# slider.net
KiCad netlist of a schematic drawn in EAGLE
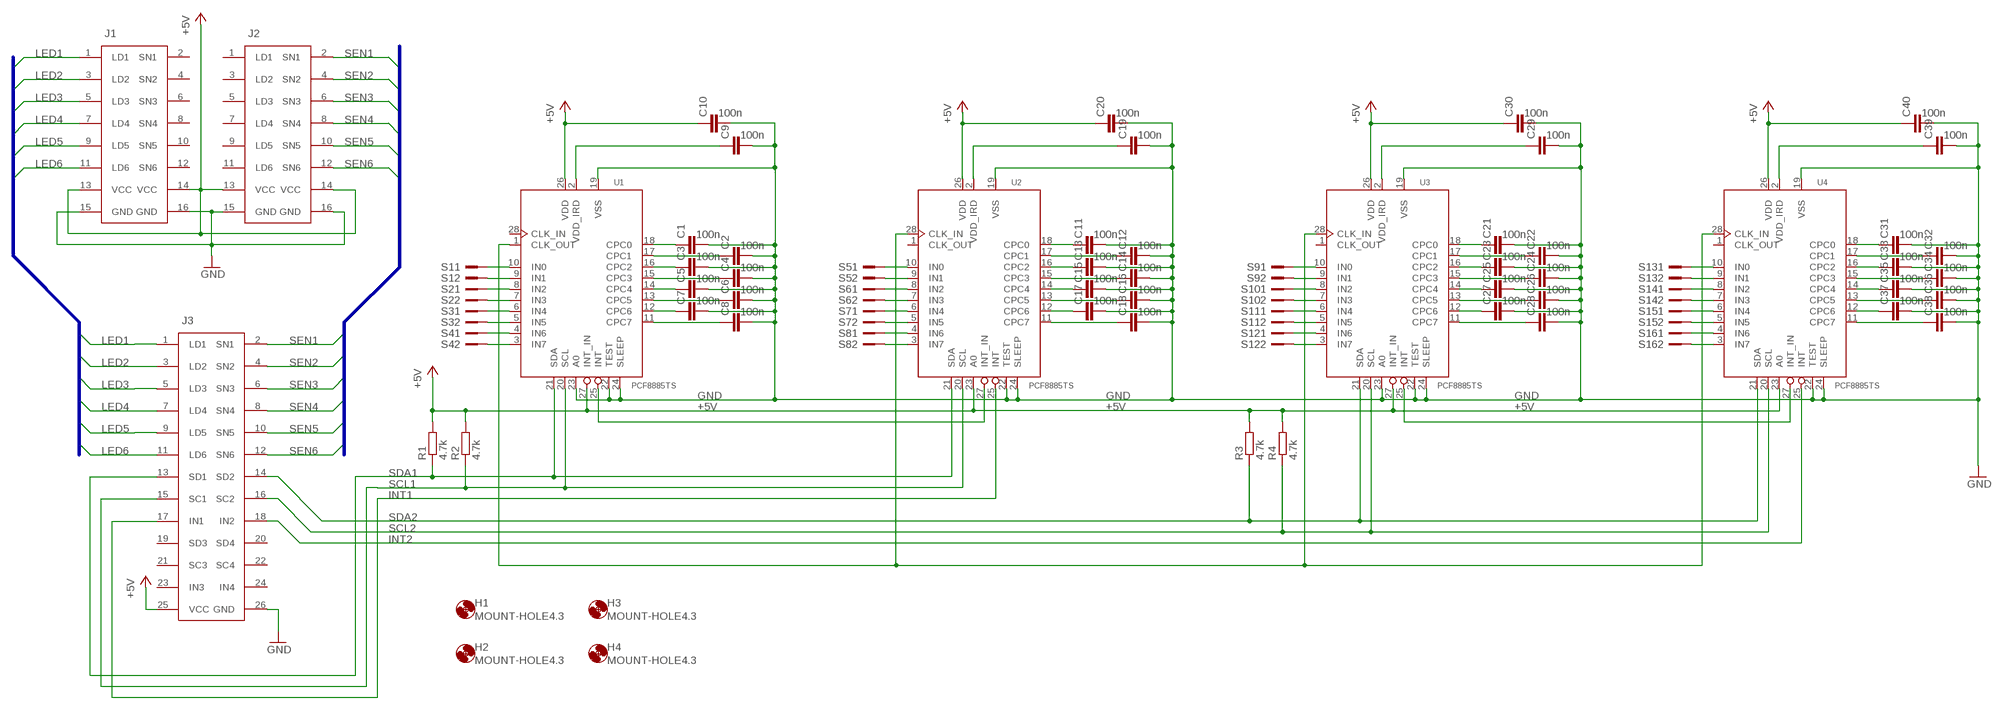
[diagram p0: schematic, sheet 1]

(export (version "E")
  (design (tool "Eeschema 10.0.6"))
  (components
    (comp (ref "C1")
      (value "100n")
      (footprint "eagle-import:C0603K")
      (libsource (lib "eagle-import") (part "C-EUC0603K"))
    )
    (comp (ref "C2")
      (value "100n")
      (footprint "eagle-import:C0603K")
      (libsource (lib "eagle-import") (part "C-EUC0603K"))
    )
    (comp (ref "C3")
      (value "100n")
      (footprint "eagle-import:C0603K")
      (libsource (lib "eagle-import") (part "C-EUC0603K"))
    )
    (comp (ref "C4")
      (value "100n")
      (footprint "eagle-import:C0603K")
      (libsource (lib "eagle-import") (part "C-EUC0603K"))
    )
    (comp (ref "C5")
      (value "100n")
      (footprint "eagle-import:C0603K")
      (libsource (lib "eagle-import") (part "C-EUC0603K"))
    )
    (comp (ref "C6")
      (value "100n")
      (footprint "eagle-import:C0603K")
      (libsource (lib "eagle-import") (part "C-EUC0603K"))
    )
    (comp (ref "C7")
      (value "100n")
      (footprint "eagle-import:C0603K")
      (libsource (lib "eagle-import") (part "C-EUC0603K"))
    )
    (comp (ref "C8")
      (value "100n")
      (footprint "eagle-import:C0603K")
      (libsource (lib "eagle-import") (part "C-EUC0603K"))
    )
    (comp (ref "C9")
      (value "100n")
      (footprint "eagle-import:C0603K")
      (libsource (lib "eagle-import") (part "C-EUC0603K"))
    )
    (comp (ref "C10")
      (value "100n")
      (footprint "eagle-import:C0603K")
      (libsource (lib "eagle-import") (part "C-EUC0603K"))
    )
    (comp (ref "C11")
      (value "100n")
      (footprint "eagle-import:C0603K")
      (libsource (lib "eagle-import") (part "C-EUC0603K"))
    )
    (comp (ref "C12")
      (value "100n")
      (footprint "eagle-import:C0603K")
      (libsource (lib "eagle-import") (part "C-EUC0603K"))
    )
    (comp (ref "C13")
      (value "100n")
      (footprint "eagle-import:C0603K")
      (libsource (lib "eagle-import") (part "C-EUC0603K"))
    )
    (comp (ref "C14")
      (value "100n")
      (footprint "eagle-import:C0603K")
      (libsource (lib "eagle-import") (part "C-EUC0603K"))
    )
    (comp (ref "C15")
      (value "100n")
      (footprint "eagle-import:C0603K")
      (libsource (lib "eagle-import") (part "C-EUC0603K"))
    )
    (comp (ref "C16")
      (value "100n")
      (footprint "eagle-import:C0603K")
      (libsource (lib "eagle-import") (part "C-EUC0603K"))
    )
    (comp (ref "C17")
      (value "100n")
      (footprint "eagle-import:C0603K")
      (libsource (lib "eagle-import") (part "C-EUC0603K"))
    )
    (comp (ref "C18")
      (value "100n")
      (footprint "eagle-import:C0603K")
      (libsource (lib "eagle-import") (part "C-EUC0603K"))
    )
    (comp (ref "C19")
      (value "100n")
      (footprint "eagle-import:C0603K")
      (libsource (lib "eagle-import") (part "C-EUC0603K"))
    )
    (comp (ref "C20")
      (value "100n")
      (footprint "eagle-import:C0603K")
      (libsource (lib "eagle-import") (part "C-EUC0603K"))
    )
    (comp (ref "C21")
      (value "100n")
      (footprint "eagle-import:C0603K")
      (libsource (lib "eagle-import") (part "C-EUC0603K"))
    )
    (comp (ref "C22")
      (value "100n")
      (footprint "eagle-import:C0603K")
      (libsource (lib "eagle-import") (part "C-EUC0603K"))
    )
    (comp (ref "C23")
      (value "100n")
      (footprint "eagle-import:C0603K")
      (libsource (lib "eagle-import") (part "C-EUC0603K"))
    )
    (comp (ref "C24")
      (value "100n")
      (footprint "eagle-import:C0603K")
      (libsource (lib "eagle-import") (part "C-EUC0603K"))
    )
    (comp (ref "C25")
      (value "100n")
      (footprint "eagle-import:C0603K")
      (libsource (lib "eagle-import") (part "C-EUC0603K"))
    )
    (comp (ref "C26")
      (value "100n")
      (footprint "eagle-import:C0603K")
      (libsource (lib "eagle-import") (part "C-EUC0603K"))
    )
    (comp (ref "C27")
      (value "100n")
      (footprint "eagle-import:C0603K")
      (libsource (lib "eagle-import") (part "C-EUC0603K"))
    )
    (comp (ref "C28")
      (value "100n")
      (footprint "eagle-import:C0603K")
      (libsource (lib "eagle-import") (part "C-EUC0603K"))
    )
    (comp (ref "C29")
      (value "100n")
      (footprint "eagle-import:C0603K")
      (libsource (lib "eagle-import") (part "C-EUC0603K"))
    )
    (comp (ref "C30")
      (value "100n")
      (footprint "eagle-import:C0603K")
      (libsource (lib "eagle-import") (part "C-EUC0603K"))
    )
    (comp (ref "C31")
      (value "100n")
      (footprint "eagle-import:C0603K")
      (libsource (lib "eagle-import") (part "C-EUC0603K"))
    )
    (comp (ref "C32")
      (value "100n")
      (footprint "eagle-import:C0603K")
      (libsource (lib "eagle-import") (part "C-EUC0603K"))
    )
    (comp (ref "C33")
      (value "100n")
      (footprint "eagle-import:C0603K")
      (libsource (lib "eagle-import") (part "C-EUC0603K"))
    )
    (comp (ref "C34")
      (value "100n")
      (footprint "eagle-import:C0603K")
      (libsource (lib "eagle-import") (part "C-EUC0603K"))
    )
    (comp (ref "C35")
      (value "100n")
      (footprint "eagle-import:C0603K")
      (libsource (lib "eagle-import") (part "C-EUC0603K"))
    )
    (comp (ref "C36")
      (value "100n")
      (footprint "eagle-import:C0603K")
      (libsource (lib "eagle-import") (part "C-EUC0603K"))
    )
    (comp (ref "C37")
      (value "100n")
      (footprint "eagle-import:C0603K")
      (libsource (lib "eagle-import") (part "C-EUC0603K"))
    )
    (comp (ref "C38")
      (value "100n")
      (footprint "eagle-import:C0603K")
      (libsource (lib "eagle-import") (part "C-EUC0603K"))
    )
    (comp (ref "C39")
      (value "100n")
      (footprint "eagle-import:C0603K")
      (libsource (lib "eagle-import") (part "C-EUC0603K"))
    )
    (comp (ref "C40")
      (value "100n")
      (footprint "eagle-import:C0603K")
      (libsource (lib "eagle-import") (part "C-EUC0603K"))
    )
    (comp (ref "H1")
      (value "MOUNT-HOLE4.3")
      (footprint "eagle-import:4,3")
      (libsource (lib "eagle-import") (part "MOUNT-HOLE4.3"))
    )
    (comp (ref "H2")
      (value "MOUNT-HOLE4.3")
      (footprint "eagle-import:4,3")
      (libsource (lib "eagle-import") (part "MOUNT-HOLE4.3"))
    )
    (comp (ref "H3")
      (value "MOUNT-HOLE4.3")
      (footprint "eagle-import:4,3")
      (libsource (lib "eagle-import") (part "MOUNT-HOLE4.3"))
    )
    (comp (ref "H4")
      (value "MOUNT-HOLE4.3")
      (footprint "eagle-import:4,3")
      (libsource (lib "eagle-import") (part "MOUNT-HOLE4.3"))
    )
    (comp (ref "J1")
      (value "2516-SMD-AIR")
      (footprint "eagle-import:612X1620621")
      (libsource (lib "eagle-import") (part "2516-SMD-AIR"))
    )
    (comp (ref "J2")
      (value "2516-SMD-AIR")
      (footprint "eagle-import:612X1620621")
      (libsource (lib "eagle-import") (part "2516-SMD-AIR"))
    )
    (comp (ref "J3")
      (value "2526-SMD-MCU")
      (footprint "eagle-import:612X2620621")
      (libsource (lib "eagle-import") (part "2526-SMD-MCU"))
    )
    (comp (ref "R1")
      (value "4.7k")
      (footprint "eagle-import:R0805")
      (libsource (lib "eagle-import") (part "R-EU_R0805"))
    )
    (comp (ref "R2")
      (value "4.7k")
      (footprint "eagle-import:R0805")
      (libsource (lib "eagle-import") (part "R-EU_R0805"))
    )
    (comp (ref "R3")
      (value "4.7k")
      (footprint "eagle-import:R0805")
      (libsource (lib "eagle-import") (part "R-EU_R0805"))
    )
    (comp (ref "R4")
      (value "4.7k")
      (footprint "eagle-import:R0805")
      (libsource (lib "eagle-import") (part "R-EU_R0805"))
    )
    (comp (ref "S1")
      (value "SENSPAD")
      (footprint "eagle-import:SENSPAD")
      (libsource (lib "eagle-import") (part "SENSPAD"))
    )
    (comp (ref "S2")
      (value "SENSPAD")
      (footprint "eagle-import:SENSPAD")
      (libsource (lib "eagle-import") (part "SENSPAD"))
    )
    (comp (ref "S3")
      (value "SENSPAD")
      (footprint "eagle-import:SENSPAD")
      (libsource (lib "eagle-import") (part "SENSPAD"))
    )
    (comp (ref "S4")
      (value "SENSPAD")
      (footprint "eagle-import:SENSPAD")
      (libsource (lib "eagle-import") (part "SENSPAD"))
    )
    (comp (ref "S5")
      (value "SENSPAD")
      (footprint "eagle-import:SENSPAD")
      (libsource (lib "eagle-import") (part "SENSPAD"))
    )
    (comp (ref "S6")
      (value "SENSPAD")
      (footprint "eagle-import:SENSPAD")
      (libsource (lib "eagle-import") (part "SENSPAD"))
    )
    (comp (ref "S7")
      (value "SENSPAD")
      (footprint "eagle-import:SENSPAD")
      (libsource (lib "eagle-import") (part "SENSPAD"))
    )
    (comp (ref "S8")
      (value "SENSPAD")
      (footprint "eagle-import:SENSPAD")
      (libsource (lib "eagle-import") (part "SENSPAD"))
    )
    (comp (ref "S9")
      (value "SENSPAD")
      (footprint "eagle-import:SENSPAD")
      (libsource (lib "eagle-import") (part "SENSPAD"))
    )
    (comp (ref "S10")
      (value "SENSPAD")
      (footprint "eagle-import:SENSPAD")
      (libsource (lib "eagle-import") (part "SENSPAD"))
    )
    (comp (ref "S11")
      (value "SENSPAD")
      (footprint "eagle-import:SENSPAD")
      (libsource (lib "eagle-import") (part "SENSPAD"))
    )
    (comp (ref "S12")
      (value "SENSPAD")
      (footprint "eagle-import:SENSPAD")
      (libsource (lib "eagle-import") (part "SENSPAD"))
    )
    (comp (ref "S13")
      (value "SENSPAD")
      (footprint "eagle-import:SENSPAD")
      (libsource (lib "eagle-import") (part "SENSPAD"))
    )
    (comp (ref "S14")
      (value "SENSPAD")
      (footprint "eagle-import:SENSPAD")
      (libsource (lib "eagle-import") (part "SENSPAD"))
    )
    (comp (ref "S15")
      (value "SENSPAD")
      (footprint "eagle-import:SENSPAD")
      (libsource (lib "eagle-import") (part "SENSPAD"))
    )
    (comp (ref "S16")
      (value "SENSPAD")
      (footprint "eagle-import:SENSPAD")
      (libsource (lib "eagle-import") (part "SENSPAD"))
    )
    (comp (ref "U1")
      (value "PCF8885TS")
      (footprint "eagle-import:SOT361-1")
      (libsource (lib "eagle-import") (part "PCF8885TS"))
    )
    (comp (ref "U2")
      (value "PCF8885TS")
      (footprint "eagle-import:SOT361-1")
      (libsource (lib "eagle-import") (part "PCF8885TS"))
    )
    (comp (ref "U3")
      (value "PCF8885TS")
      (footprint "eagle-import:SOT361-1")
      (libsource (lib "eagle-import") (part "PCF8885TS"))
    )
    (comp (ref "U4")
      (value "PCF8885TS")
      (footprint "eagle-import:SOT361-1")
      (libsource (lib "eagle-import") (part "PCF8885TS"))
    )
  )
  (nets
    (net (code "1") (name "+5V") (class "Default")
      (node (ref "C10") (pin "1") (pinfunction "1_1") (pintype "passive"))
      (node (ref "C20") (pin "1") (pinfunction "1_1") (pintype "passive"))
      (node (ref "C30") (pin "1") (pinfunction "1_1") (pintype "passive"))
      (node (ref "C40") (pin "1") (pinfunction "1_1") (pintype "passive"))
      (node (ref "J1") (pin "13") (pinfunction "VCC_13") (pintype "passive"))
      (node (ref "J1") (pin "14") (pinfunction "VCC_14") (pintype "passive"))
      (node (ref "J2") (pin "13") (pinfunction "VCC_13") (pintype "passive"))
      (node (ref "J2") (pin "14") (pinfunction "VCC_14") (pintype "passive"))
      (node (ref "J3") (pin "25") (pinfunction "VCC_25") (pintype "passive"))
      (node (ref "R1") (pin "2") (pinfunction "2_2") (pintype "passive"))
      (node (ref "R2") (pin "2") (pinfunction "2_2") (pintype "passive"))
      (node (ref "R3") (pin "2") (pinfunction "2_2") (pintype "passive"))
      (node (ref "R4") (pin "2") (pinfunction "2_2") (pintype "passive"))
      (node (ref "U1") (pin "26") (pinfunction "VDD_26") (pintype "power_in"))
      (node (ref "U1") (pin "27") (pinfunction "INT_IN_27") (pintype "input"))
      (node (ref "U2") (pin "23") (pinfunction "A0_23") (pintype "input"))
      (node (ref "U2") (pin "26") (pinfunction "VDD_26") (pintype "power_in"))
      (node (ref "U3") (pin "26") (pinfunction "VDD_26") (pintype "power_in"))
      (node (ref "U3") (pin "27") (pinfunction "INT_IN_27") (pintype "input"))
      (node (ref "U4") (pin "23") (pinfunction "A0_23") (pintype "input"))
      (node (ref "U4") (pin "26") (pinfunction "VDD_26") (pintype "power_in"))
    )
    (net (code "2") (name "/INT1") (class "Default")
      (node (ref "J3") (pin "17") (pinfunction "IN1_17") (pintype "passive"))
      (node (ref "U2") (pin "25") (pinfunction "INT_25") (pintype "output"))
    )
    (net (code "3") (name "/INT2") (class "Default")
      (node (ref "J3") (pin "18") (pinfunction "IN2_18") (pintype "passive"))
      (node (ref "U4") (pin "25") (pinfunction "INT_25") (pintype "output"))
    )
    (net (code "4") (name "/LED1") (class "Default")
      (node (ref "J1") (pin "1") (pinfunction "LD1_1") (pintype "passive"))
      (node (ref "J3") (pin "1") (pinfunction "LD1_1") (pintype "passive"))
    )
    (net (code "5") (name "/LED2") (class "Default")
      (node (ref "J1") (pin "3") (pinfunction "LD2_3") (pintype "passive"))
      (node (ref "J3") (pin "3") (pinfunction "LD2_3") (pintype "passive"))
    )
    (net (code "6") (name "/LED3") (class "Default")
      (node (ref "J1") (pin "5") (pinfunction "LD3_5") (pintype "passive"))
      (node (ref "J3") (pin "5") (pinfunction "LD3_5") (pintype "passive"))
    )
    (net (code "7") (name "/LED4") (class "Default")
      (node (ref "J1") (pin "7") (pinfunction "LD4_7") (pintype "passive"))
      (node (ref "J3") (pin "7") (pinfunction "LD4_7") (pintype "passive"))
    )
    (net (code "8") (name "/LED5") (class "Default")
      (node (ref "J1") (pin "9") (pinfunction "LD5_9") (pintype "passive"))
      (node (ref "J3") (pin "9") (pinfunction "LD5_9") (pintype "passive"))
    )
    (net (code "9") (name "/LED6") (class "Default")
      (node (ref "J1") (pin "11") (pinfunction "LD6_11") (pintype "passive"))
      (node (ref "J3") (pin "11") (pinfunction "LD6_11") (pintype "passive"))
    )
    (net (code "10") (name "/SCL1") (class "Default")
      (node (ref "J3") (pin "15") (pinfunction "SC1_15") (pintype "passive"))
      (node (ref "R2") (pin "1") (pinfunction "1_1") (pintype "passive"))
      (node (ref "U1") (pin "20") (pinfunction "SCL_20") (pintype "input"))
      (node (ref "U2") (pin "20") (pinfunction "SCL_20") (pintype "input"))
    )
    (net (code "11") (name "/SCL2") (class "Default")
      (node (ref "J3") (pin "16") (pinfunction "SC2_16") (pintype "passive"))
      (node (ref "R4") (pin "1") (pinfunction "1_1") (pintype "passive"))
      (node (ref "U3") (pin "20") (pinfunction "SCL_20") (pintype "input"))
      (node (ref "U4") (pin "20") (pinfunction "SCL_20") (pintype "input"))
    )
    (net (code "12") (name "/SDA1") (class "Default")
      (node (ref "J3") (pin "13") (pinfunction "SD1_13") (pintype "passive"))
      (node (ref "R1") (pin "1") (pinfunction "1_1") (pintype "passive"))
      (node (ref "U1") (pin "21") (pinfunction "SDA_21") (pintype "bidirectional"))
      (node (ref "U2") (pin "21") (pinfunction "SDA_21") (pintype "bidirectional"))
    )
    (net (code "13") (name "/SDA2") (class "Default")
      (node (ref "J3") (pin "14") (pinfunction "SD2_14") (pintype "passive"))
      (node (ref "R3") (pin "1") (pinfunction "1_1") (pintype "passive"))
      (node (ref "U3") (pin "21") (pinfunction "SDA_21") (pintype "bidirectional"))
      (node (ref "U4") (pin "21") (pinfunction "SDA_21") (pintype "bidirectional"))
    )
    (net (code "14") (name "/SEN1") (class "Default")
      (node (ref "J2") (pin "2") (pinfunction "SN1_2") (pintype "passive"))
      (node (ref "J3") (pin "2") (pinfunction "SN1_2") (pintype "passive"))
    )
    (net (code "15") (name "/SEN2") (class "Default")
      (node (ref "J2") (pin "4") (pinfunction "SN2_4") (pintype "passive"))
      (node (ref "J3") (pin "4") (pinfunction "SN2_4") (pintype "passive"))
    )
    (net (code "16") (name "/SEN3") (class "Default")
      (node (ref "J2") (pin "6") (pinfunction "SN3_6") (pintype "passive"))
      (node (ref "J3") (pin "6") (pinfunction "SN3_6") (pintype "passive"))
    )
    (net (code "17") (name "/SEN4") (class "Default")
      (node (ref "J2") (pin "8") (pinfunction "SN4_8") (pintype "passive"))
      (node (ref "J3") (pin "8") (pinfunction "SN4_8") (pintype "passive"))
    )
    (net (code "18") (name "/SEN5") (class "Default")
      (node (ref "J2") (pin "10") (pinfunction "SN5_10") (pintype "passive"))
      (node (ref "J3") (pin "10") (pinfunction "SN5_10") (pintype "passive"))
    )
    (net (code "19") (name "/SEN6") (class "Default")
      (node (ref "J2") (pin "12") (pinfunction "SN6_12") (pintype "passive"))
      (node (ref "J3") (pin "12") (pinfunction "SN6_12") (pintype "passive"))
    )
    (net (code "20") (name "GND") (class "Default")
      (node (ref "C1") (pin "2") (pinfunction "2_2") (pintype "passive"))
      (node (ref "C10") (pin "2") (pinfunction "2_2") (pintype "passive"))
      (node (ref "C11") (pin "2") (pinfunction "2_2") (pintype "passive"))
      (node (ref "C12") (pin "2") (pinfunction "2_2") (pintype "passive"))
      (node (ref "C13") (pin "2") (pinfunction "2_2") (pintype "passive"))
      (node (ref "C14") (pin "2") (pinfunction "2_2") (pintype "passive"))
      (node (ref "C15") (pin "2") (pinfunction "2_2") (pintype "passive"))
      (node (ref "C16") (pin "2") (pinfunction "2_2") (pintype "passive"))
      (node (ref "C17") (pin "2") (pinfunction "2_2") (pintype "passive"))
      (node (ref "C18") (pin "2") (pinfunction "2_2") (pintype "passive"))
      (node (ref "C19") (pin "2") (pinfunction "2_2") (pintype "passive"))
      (node (ref "C2") (pin "2") (pinfunction "2_2") (pintype "passive"))
      (node (ref "C20") (pin "2") (pinfunction "2_2") (pintype "passive"))
      (node (ref "C21") (pin "2") (pinfunction "2_2") (pintype "passive"))
      (node (ref "C22") (pin "2") (pinfunction "2_2") (pintype "passive"))
      (node (ref "C23") (pin "2") (pinfunction "2_2") (pintype "passive"))
      (node (ref "C24") (pin "2") (pinfunction "2_2") (pintype "passive"))
      (node (ref "C25") (pin "2") (pinfunction "2_2") (pintype "passive"))
      (node (ref "C26") (pin "2") (pinfunction "2_2") (pintype "passive"))
      (node (ref "C27") (pin "2") (pinfunction "2_2") (pintype "passive"))
      (node (ref "C28") (pin "2") (pinfunction "2_2") (pintype "passive"))
      (node (ref "C29") (pin "2") (pinfunction "2_2") (pintype "passive"))
      (node (ref "C3") (pin "2") (pinfunction "2_2") (pintype "passive"))
      (node (ref "C30") (pin "2") (pinfunction "2_2") (pintype "passive"))
      (node (ref "C31") (pin "2") (pinfunction "2_2") (pintype "passive"))
      (node (ref "C32") (pin "2") (pinfunction "2_2") (pintype "passive"))
      (node (ref "C33") (pin "2") (pinfunction "2_2") (pintype "passive"))
      (node (ref "C34") (pin "2") (pinfunction "2_2") (pintype "passive"))
      (node (ref "C35") (pin "2") (pinfunction "2_2") (pintype "passive"))
      (node (ref "C36") (pin "2") (pinfunction "2_2") (pintype "passive"))
      (node (ref "C37") (pin "2") (pinfunction "2_2") (pintype "passive"))
      (node (ref "C38") (pin "2") (pinfunction "2_2") (pintype "passive"))
      (node (ref "C39") (pin "2") (pinfunction "2_2") (pintype "passive"))
      (node (ref "C4") (pin "2") (pinfunction "2_2") (pintype "passive"))
      (node (ref "C40") (pin "2") (pinfunction "2_2") (pintype "passive"))
      (node (ref "C5") (pin "2") (pinfunction "2_2") (pintype "passive"))
      (node (ref "C6") (pin "2") (pinfunction "2_2") (pintype "passive"))
      (node (ref "C7") (pin "2") (pinfunction "2_2") (pintype "passive"))
      (node (ref "C8") (pin "2") (pinfunction "2_2") (pintype "passive"))
      (node (ref "C9") (pin "2") (pinfunction "2_2") (pintype "passive"))
      (node (ref "J1") (pin "15") (pinfunction "GND_15") (pintype "passive"))
      (node (ref "J1") (pin "16") (pinfunction "GND_16") (pintype "passive"))
      (node (ref "J2") (pin "15") (pinfunction "GND_15") (pintype "passive"))
      (node (ref "J2") (pin "16") (pinfunction "GND_16") (pintype "passive"))
      (node (ref "J3") (pin "26") (pinfunction "GND_26") (pintype "passive"))
      (node (ref "U1") (pin "19") (pinfunction "VSS_19") (pintype "power_in"))
      (node (ref "U1") (pin "22") (pinfunction "TEST_22") (pintype "input"))
      (node (ref "U1") (pin "23") (pinfunction "A0_23") (pintype "input"))
      (node (ref "U1") (pin "24") (pinfunction "SLEEP_24") (pintype "input"))
      (node (ref "U2") (pin "19") (pinfunction "VSS_19") (pintype "power_in"))
      (node (ref "U2") (pin "22") (pinfunction "TEST_22") (pintype "input"))
      (node (ref "U2") (pin "24") (pinfunction "SLEEP_24") (pintype "input"))
      (node (ref "U3") (pin "19") (pinfunction "VSS_19") (pintype "power_in"))
      (node (ref "U3") (pin "22") (pinfunction "TEST_22") (pintype "input"))
      (node (ref "U3") (pin "23") (pinfunction "A0_23") (pintype "input"))
      (node (ref "U3") (pin "24") (pinfunction "SLEEP_24") (pintype "input"))
      (node (ref "U4") (pin "19") (pinfunction "VSS_19") (pintype "power_in"))
      (node (ref "U4") (pin "22") (pinfunction "TEST_22") (pintype "input"))
      (node (ref "U4") (pin "24") (pinfunction "SLEEP_24") (pintype "input"))
    )
    (net (code "21") (name "Net-(S1A-KL)") (class "Default")
      (node (ref "S1") (pin "1") (pinfunction "KL_1") (pintype "passive"))
      (node (ref "U1") (pin "10") (pinfunction "IN0_10") (pintype "input"))
    )
    (net (code "22") (name "Net-(S1B-KL)") (class "Default")
      (node (ref "S1") (pin "2") (pinfunction "KL_2") (pintype "passive"))
      (node (ref "U1") (pin "9") (pinfunction "IN1_9") (pintype "input"))
    )
    (net (code "23") (name "Net-(S2A-KL)") (class "Default")
      (node (ref "S2") (pin "1") (pinfunction "KL_1") (pintype "passive"))
      (node (ref "U1") (pin "8") (pinfunction "IN2_8") (pintype "input"))
    )
    (net (code "24") (name "Net-(S2B-KL)") (class "Default")
      (node (ref "S2") (pin "2") (pinfunction "KL_2") (pintype "passive"))
      (node (ref "U1") (pin "7") (pinfunction "IN3_7") (pintype "input"))
    )
    (net (code "25") (name "Net-(S3A-KL)") (class "Default")
      (node (ref "S3") (pin "1") (pinfunction "KL_1") (pintype "passive"))
      (node (ref "U1") (pin "6") (pinfunction "IN4_6") (pintype "input"))
    )
    (net (code "26") (name "Net-(S3B-KL)") (class "Default")
      (node (ref "S3") (pin "2") (pinfunction "KL_2") (pintype "passive"))
      (node (ref "U1") (pin "5") (pinfunction "IN5_5") (pintype "input"))
    )
    (net (code "27") (name "Net-(S4A-KL)") (class "Default")
      (node (ref "S4") (pin "1") (pinfunction "KL_1") (pintype "passive"))
      (node (ref "U1") (pin "4") (pinfunction "IN6_4") (pintype "input"))
    )
    (net (code "28") (name "Net-(S4B-KL)") (class "Default")
      (node (ref "S4") (pin "2") (pinfunction "KL_2") (pintype "passive"))
      (node (ref "U1") (pin "3") (pinfunction "IN7_3") (pintype "input"))
    )
    (net (code "29") (name "Net-(S5A-KL)") (class "Default")
      (node (ref "S5") (pin "1") (pinfunction "KL_1") (pintype "passive"))
      (node (ref "U2") (pin "10") (pinfunction "IN0_10") (pintype "input"))
    )
    (net (code "30") (name "Net-(S5B-KL)") (class "Default")
      (node (ref "S5") (pin "2") (pinfunction "KL_2") (pintype "passive"))
      (node (ref "U2") (pin "9") (pinfunction "IN1_9") (pintype "input"))
    )
    (net (code "31") (name "Net-(S6A-KL)") (class "Default")
      (node (ref "S6") (pin "1") (pinfunction "KL_1") (pintype "passive"))
      (node (ref "U2") (pin "8") (pinfunction "IN2_8") (pintype "input"))
    )
    (net (code "32") (name "Net-(S6B-KL)") (class "Default")
      (node (ref "S6") (pin "2") (pinfunction "KL_2") (pintype "passive"))
      (node (ref "U2") (pin "7") (pinfunction "IN3_7") (pintype "input"))
    )
    (net (code "33") (name "Net-(S7A-KL)") (class "Default")
      (node (ref "S7") (pin "1") (pinfunction "KL_1") (pintype "passive"))
      (node (ref "U2") (pin "6") (pinfunction "IN4_6") (pintype "input"))
    )
    (net (code "34") (name "Net-(S7B-KL)") (class "Default")
      (node (ref "S7") (pin "2") (pinfunction "KL_2") (pintype "passive"))
      (node (ref "U2") (pin "5") (pinfunction "IN5_5") (pintype "input"))
    )
    (net (code "35") (name "Net-(S8A-KL)") (class "Default")
      (node (ref "S8") (pin "1") (pinfunction "KL_1") (pintype "passive"))
      (node (ref "U2") (pin "4") (pinfunction "IN6_4") (pintype "input"))
    )
    (net (code "36") (name "Net-(S8B-KL)") (class "Default")
      (node (ref "S8") (pin "2") (pinfunction "KL_2") (pintype "passive"))
      (node (ref "U2") (pin "3") (pinfunction "IN7_3") (pintype "input"))
    )
    (net (code "37") (name "Net-(S9A-KL)") (class "Default")
      (node (ref "S9") (pin "1") (pinfunction "KL_1") (pintype "passive"))
      (node (ref "U3") (pin "10") (pinfunction "IN0_10") (pintype "input"))
    )
    (net (code "38") (name "Net-(S9B-KL)") (class "Default")
      (node (ref "S9") (pin "2") (pinfunction "KL_2") (pintype "passive"))
      (node (ref "U3") (pin "9") (pinfunction "IN1_9") (pintype "input"))
    )
    (net (code "39") (name "Net-(S10A-KL)") (class "Default")
      (node (ref "S10") (pin "1") (pinfunction "KL_1") (pintype "passive"))
      (node (ref "U3") (pin "8") (pinfunction "IN2_8") (pintype "input"))
    )
    (net (code "40") (name "Net-(S10B-KL)") (class "Default")
      (node (ref "S10") (pin "2") (pinfunction "KL_2") (pintype "passive"))
      (node (ref "U3") (pin "7") (pinfunction "IN3_7") (pintype "input"))
    )
    (net (code "41") (name "Net-(S11A-KL)") (class "Default")
      (node (ref "S11") (pin "1") (pinfunction "KL_1") (pintype "passive"))
      (node (ref "U3") (pin "6") (pinfunction "IN4_6") (pintype "input"))
    )
    (net (code "42") (name "Net-(S11B-KL)") (class "Default")
      (node (ref "S11") (pin "2") (pinfunction "KL_2") (pintype "passive"))
      (node (ref "U3") (pin "5") (pinfunction "IN5_5") (pintype "input"))
    )
    (net (code "43") (name "Net-(S12A-KL)") (class "Default")
      (node (ref "S12") (pin "1") (pinfunction "KL_1") (pintype "passive"))
      (node (ref "U3") (pin "4") (pinfunction "IN6_4") (pintype "input"))
    )
    (net (code "44") (name "Net-(S12B-KL)") (class "Default")
      (node (ref "S12") (pin "2") (pinfunction "KL_2") (pintype "passive"))
      (node (ref "U3") (pin "3") (pinfunction "IN7_3") (pintype "input"))
    )
    (net (code "45") (name "Net-(S13A-KL)") (class "Default")
      (node (ref "S13") (pin "1") (pinfunction "KL_1") (pintype "passive"))
      (node (ref "U4") (pin "10") (pinfunction "IN0_10") (pintype "input"))
    )
    (net (code "46") (name "Net-(S13B-KL)") (class "Default")
      (node (ref "S13") (pin "2") (pinfunction "KL_2") (pintype "passive"))
      (node (ref "U4") (pin "9") (pinfunction "IN1_9") (pintype "input"))
    )
    (net (code "47") (name "Net-(S14A-KL)") (class "Default")
      (node (ref "S14") (pin "1") (pinfunction "KL_1") (pintype "passive"))
      (node (ref "U4") (pin "8") (pinfunction "IN2_8") (pintype "input"))
    )
    (net (code "48") (name "Net-(S14B-KL)") (class "Default")
      (node (ref "S14") (pin "2") (pinfunction "KL_2") (pintype "passive"))
      (node (ref "U4") (pin "7") (pinfunction "IN3_7") (pintype "input"))
    )
    (net (code "49") (name "Net-(S15A-KL)") (class "Default")
      (node (ref "S15") (pin "1") (pinfunction "KL_1") (pintype "passive"))
      (node (ref "U4") (pin "6") (pinfunction "IN4_6") (pintype "input"))
    )
    (net (code "50") (name "Net-(S15B-KL)") (class "Default")
      (node (ref "S15") (pin "2") (pinfunction "KL_2") (pintype "passive"))
      (node (ref "U4") (pin "5") (pinfunction "IN5_5") (pintype "input"))
    )
    (net (code "51") (name "Net-(S16A-KL)") (class "Default")
      (node (ref "S16") (pin "1") (pinfunction "KL_1") (pintype "passive"))
      (node (ref "U4") (pin "4") (pinfunction "IN6_4") (pintype "input"))
    )
    (net (code "52") (name "Net-(S16B-KL)") (class "Default")
      (node (ref "S16") (pin "2") (pinfunction "KL_2") (pintype "passive"))
      (node (ref "U4") (pin "3") (pinfunction "IN7_3") (pintype "input"))
    )
    (net (code "53") (name "Net-(U1-CLK_OUT)") (class "Default")
      (node (ref "U1") (pin "1") (pinfunction "CLK_OUT_1") (pintype "output"))
      (node (ref "U2") (pin "28") (pinfunction "CLK_IN_28") (pintype "input"))
      (node (ref "U3") (pin "28") (pinfunction "CLK_IN_28") (pintype "input"))
      (node (ref "U4") (pin "28") (pinfunction "CLK_IN_28") (pintype "input"))
    )
    (net (code "54") (name "Net-(U1-CPC0)") (class "Default")
      (node (ref "C1") (pin "1") (pinfunction "1_1") (pintype "passive"))
      (node (ref "U1") (pin "18") (pinfunction "CPC0_18") (pintype "passive"))
    )
    (net (code "55") (name "Net-(U1-CPC1)") (class "Default")
      (node (ref "C2") (pin "1") (pinfunction "1_1") (pintype "passive"))
      (node (ref "U1") (pin "17") (pinfunction "CPC1_17") (pintype "passive"))
    )
    (net (code "56") (name "Net-(U1-CPC2)") (class "Default")
      (node (ref "C3") (pin "1") (pinfunction "1_1") (pintype "passive"))
      (node (ref "U1") (pin "16") (pinfunction "CPC2_16") (pintype "passive"))
    )
    (net (code "57") (name "Net-(U1-CPC3)") (class "Default")
      (node (ref "C4") (pin "1") (pinfunction "1_1") (pintype "passive"))
      (node (ref "U1") (pin "15") (pinfunction "CPC3_15") (pintype "passive"))
    )
    (net (code "58") (name "Net-(U1-CPC4)") (class "Default")
      (node (ref "C5") (pin "1") (pinfunction "1_1") (pintype "passive"))
      (node (ref "U1") (pin "14") (pinfunction "CPC4_14") (pintype "passive"))
    )
    (net (code "59") (name "Net-(U1-CPC5)") (class "Default")
      (node (ref "C6") (pin "1") (pinfunction "1_1") (pintype "passive"))
      (node (ref "U1") (pin "13") (pinfunction "CPC5_13") (pintype "passive"))
    )
    (net (code "60") (name "Net-(U1-CPC6)") (class "Default")
      (node (ref "C7") (pin "1") (pinfunction "1_1") (pintype "passive"))
      (node (ref "U1") (pin "12") (pinfunction "CPC6_12") (pintype "passive"))
    )
    (net (code "61") (name "Net-(U1-CPC7)") (class "Default")
      (node (ref "C8") (pin "1") (pinfunction "1_1") (pintype "passive"))
      (node (ref "U1") (pin "11") (pinfunction "CPC7_11") (pintype "passive"))
    )
    (net (code "62") (name "Net-(U1-INT)") (class "Default")
      (node (ref "U1") (pin "25") (pinfunction "INT_25") (pintype "output"))
      (node (ref "U2") (pin "27") (pinfunction "INT_IN_27") (pintype "input"))
    )
    (net (code "63") (name "Net-(U1-VDD_IRD)") (class "Default")
      (node (ref "C9") (pin "1") (pinfunction "1_1") (pintype "passive"))
      (node (ref "U1") (pin "2") (pinfunction "VDD_IRD_2") (pintype "power_in"))
    )
    (net (code "64") (name "Net-(U2-CPC0)") (class "Default")
      (node (ref "C11") (pin "1") (pinfunction "1_1") (pintype "passive"))
      (node (ref "U2") (pin "18") (pinfunction "CPC0_18") (pintype "passive"))
    )
    (net (code "65") (name "Net-(U2-CPC1)") (class "Default")
      (node (ref "C12") (pin "1") (pinfunction "1_1") (pintype "passive"))
      (node (ref "U2") (pin "17") (pinfunction "CPC1_17") (pintype "passive"))
    )
    (net (code "66") (name "Net-(U2-CPC2)") (class "Default")
      (node (ref "C13") (pin "1") (pinfunction "1_1") (pintype "passive"))
      (node (ref "U2") (pin "16") (pinfunction "CPC2_16") (pintype "passive"))
    )
    (net (code "67") (name "Net-(U2-CPC3)") (class "Default")
      (node (ref "C14") (pin "1") (pinfunction "1_1") (pintype "passive"))
      (node (ref "U2") (pin "15") (pinfunction "CPC3_15") (pintype "passive"))
    )
    (net (code "68") (name "Net-(U2-CPC4)") (class "Default")
      (node (ref "C15") (pin "1") (pinfunction "1_1") (pintype "passive"))
      (node (ref "U2") (pin "14") (pinfunction "CPC4_14") (pintype "passive"))
    )
    (net (code "69") (name "Net-(U2-CPC5)") (class "Default")
      (node (ref "C16") (pin "1") (pinfunction "1_1") (pintype "passive"))
      (node (ref "U2") (pin "13") (pinfunction "CPC5_13") (pintype "passive"))
    )
    (net (code "70") (name "Net-(U2-CPC6)") (class "Default")
      (node (ref "C17") (pin "1") (pinfunction "1_1") (pintype "passive"))
      (node (ref "U2") (pin "12") (pinfunction "CPC6_12") (pintype "passive"))
    )
    (net (code "71") (name "Net-(U2-CPC7)") (class "Default")
      (node (ref "C18") (pin "1") (pinfunction "1_1") (pintype "passive"))
      (node (ref "U2") (pin "11") (pinfunction "CPC7_11") (pintype "passive"))
    )
    (net (code "72") (name "Net-(U2-VDD_IRD)") (class "Default")
      (node (ref "C19") (pin "1") (pinfunction "1_1") (pintype "passive"))
      (node (ref "U2") (pin "2") (pinfunction "VDD_IRD_2") (pintype "power_in"))
    )
    (net (code "73") (name "Net-(U3-CPC0)") (class "Default")
      (node (ref "C21") (pin "1") (pinfunction "1_1") (pintype "passive"))
      (node (ref "U3") (pin "18") (pinfunction "CPC0_18") (pintype "passive"))
    )
    (net (code "74") (name "Net-(U3-CPC1)") (class "Default")
      (node (ref "C22") (pin "1") (pinfunction "1_1") (pintype "passive"))
      (node (ref "U3") (pin "17") (pinfunction "CPC1_17") (pintype "passive"))
    )
    (net (code "75") (name "Net-(U3-CPC2)") (class "Default")
      (node (ref "C23") (pin "1") (pinfunction "1_1") (pintype "passive"))
      (node (ref "U3") (pin "16") (pinfunction "CPC2_16") (pintype "passive"))
    )
    (net (code "76") (name "Net-(U3-CPC3)") (class "Default")
      (node (ref "C24") (pin "1") (pinfunction "1_1") (pintype "passive"))
      (node (ref "U3") (pin "15") (pinfunction "CPC3_15") (pintype "passive"))
    )
    (net (code "77") (name "Net-(U3-CPC4)") (class "Default")
      (node (ref "C25") (pin "1") (pinfunction "1_1") (pintype "passive"))
      (node (ref "U3") (pin "14") (pinfunction "CPC4_14") (pintype "passive"))
    )
    (net (code "78") (name "Net-(U3-CPC5)") (class "Default")
      (node (ref "C26") (pin "1") (pinfunction "1_1") (pintype "passive"))
      (node (ref "U3") (pin "13") (pinfunction "CPC5_13") (pintype "passive"))
    )
    (net (code "79") (name "Net-(U3-CPC6)") (class "Default")
      (node (ref "C27") (pin "1") (pinfunction "1_1") (pintype "passive"))
      (node (ref "U3") (pin "12") (pinfunction "CPC6_12") (pintype "passive"))
    )
    (net (code "80") (name "Net-(U3-CPC7)") (class "Default")
      (node (ref "C28") (pin "1") (pinfunction "1_1") (pintype "passive"))
      (node (ref "U3") (pin "11") (pinfunction "CPC7_11") (pintype "passive"))
    )
    (net (code "81") (name "Net-(U3-INT)") (class "Default")
      (node (ref "U3") (pin "25") (pinfunction "INT_25") (pintype "output"))
      (node (ref "U4") (pin "27") (pinfunction "INT_IN_27") (pintype "input"))
    )
    (net (code "82") (name "Net-(U3-VDD_IRD)") (class "Default")
      (node (ref "C29") (pin "1") (pinfunction "1_1") (pintype "passive"))
      (node (ref "U3") (pin "2") (pinfunction "VDD_IRD_2") (pintype "power_in"))
    )
    (net (code "83") (name "Net-(U4-CPC0)") (class "Default")
      (node (ref "C31") (pin "1") (pinfunction "1_1") (pintype "passive"))
      (node (ref "U4") (pin "18") (pinfunction "CPC0_18") (pintype "passive"))
    )
    (net (code "84") (name "Net-(U4-CPC1)") (class "Default")
      (node (ref "C32") (pin "1") (pinfunction "1_1") (pintype "passive"))
      (node (ref "U4") (pin "17") (pinfunction "CPC1_17") (pintype "passive"))
    )
    (net (code "85") (name "Net-(U4-CPC2)") (class "Default")
      (node (ref "C33") (pin "1") (pinfunction "1_1") (pintype "passive"))
      (node (ref "U4") (pin "16") (pinfunction "CPC2_16") (pintype "passive"))
    )
    (net (code "86") (name "Net-(U4-CPC3)") (class "Default")
      (node (ref "C34") (pin "1") (pinfunction "1_1") (pintype "passive"))
      (node (ref "U4") (pin "15") (pinfunction "CPC3_15") (pintype "passive"))
    )
    (net (code "87") (name "Net-(U4-CPC4)") (class "Default")
      (node (ref "C35") (pin "1") (pinfunction "1_1") (pintype "passive"))
      (node (ref "U4") (pin "14") (pinfunction "CPC4_14") (pintype "passive"))
    )
    (net (code "88") (name "Net-(U4-CPC5)") (class "Default")
      (node (ref "C36") (pin "1") (pinfunction "1_1") (pintype "passive"))
      (node (ref "U4") (pin "13") (pinfunction "CPC5_13") (pintype "passive"))
    )
    (net (code "89") (name "Net-(U4-CPC6)") (class "Default")
      (node (ref "C37") (pin "1") (pinfunction "1_1") (pintype "passive"))
      (node (ref "U4") (pin "12") (pinfunction "CPC6_12") (pintype "passive"))
    )
    (net (code "90") (name "Net-(U4-CPC7)") (class "Default")
      (node (ref "C38") (pin "1") (pinfunction "1_1") (pintype "passive"))
      (node (ref "U4") (pin "11") (pinfunction "CPC7_11") (pintype "passive"))
    )
    (net (code "91") (name "Net-(U4-VDD_IRD)") (class "Default")
      (node (ref "C39") (pin "1") (pinfunction "1_1") (pintype "passive"))
      (node (ref "U4") (pin "2") (pinfunction "VDD_IRD_2") (pintype "power_in"))
    )
    (net (code "92") (name "unconnected-(J1-SN1-Pad2)") (class "Default")
      (node (ref "J1") (pin "2") (pinfunction "SN1_2") (pintype "passive"))
    )
    (net (code "93") (name "unconnected-(J1-SN2-Pad4)") (class "Default")
      (node (ref "J1") (pin "4") (pinfunction "SN2_4") (pintype "passive"))
    )
    (net (code "94") (name "unconnected-(J1-SN3-Pad6)") (class "Default")
      (node (ref "J1") (pin "6") (pinfunction "SN3_6") (pintype "passive"))
    )
    (net (code "95") (name "unconnected-(J1-SN4-Pad8)") (class "Default")
      (node (ref "J1") (pin "8") (pinfunction "SN4_8") (pintype "passive"))
    )
    (net (code "96") (name "unconnected-(J1-SN5-Pad10)") (class "Default")
      (node (ref "J1") (pin "10") (pinfunction "SN5_10") (pintype "passive"))
    )
    (net (code "97") (name "unconnected-(J1-SN6-Pad12)") (class "Default")
      (node (ref "J1") (pin "12") (pinfunction "SN6_12") (pintype "passive"))
    )
    (net (code "98") (name "unconnected-(J2-LD1-Pad1)") (class "Default")
      (node (ref "J2") (pin "1") (pinfunction "LD1_1") (pintype "passive"))
    )
    (net (code "99") (name "unconnected-(J2-LD2-Pad3)") (class "Default")
      (node (ref "J2") (pin "3") (pinfunction "LD2_3") (pintype "passive"))
    )
    (net (code "100") (name "unconnected-(J2-LD3-Pad5)") (class "Default")
      (node (ref "J2") (pin "5") (pinfunction "LD3_5") (pintype "passive"))
    )
    (net (code "101") (name "unconnected-(J2-LD4-Pad7)") (class "Default")
      (node (ref "J2") (pin "7") (pinfunction "LD4_7") (pintype "passive"))
    )
    (net (code "102") (name "unconnected-(J2-LD5-Pad9)") (class "Default")
      (node (ref "J2") (pin "9") (pinfunction "LD5_9") (pintype "passive"))
    )
    (net (code "103") (name "unconnected-(J2-LD6-Pad11)") (class "Default")
      (node (ref "J2") (pin "11") (pinfunction "LD6_11") (pintype "passive"))
    )
    (net (code "104") (name "unconnected-(J3-IN3-Pad23)") (class "Default")
      (node (ref "J3") (pin "23") (pinfunction "IN3_23") (pintype "passive"))
    )
    (net (code "105") (name "unconnected-(J3-IN4-Pad24)") (class "Default")
      (node (ref "J3") (pin "24") (pinfunction "IN4_24") (pintype "passive"))
    )
    (net (code "106") (name "unconnected-(J3-SC3-Pad21)") (class "Default")
      (node (ref "J3") (pin "21") (pinfunction "SC3_21") (pintype "passive"))
    )
    (net (code "107") (name "unconnected-(J3-SC4-Pad22)") (class "Default")
      (node (ref "J3") (pin "22") (pinfunction "SC4_22") (pintype "passive"))
    )
    (net (code "108") (name "unconnected-(J3-SD3-Pad19)") (class "Default")
      (node (ref "J3") (pin "19") (pinfunction "SD3_19") (pintype "passive"))
    )
    (net (code "109") (name "unconnected-(J3-SD4-Pad20)") (class "Default")
      (node (ref "J3") (pin "20") (pinfunction "SD4_20") (pintype "passive"))
    )
    (net (code "110") (name "unconnected-(U1-CLK_IN-Pad28)") (class "Default")
      (node (ref "U1") (pin "28") (pinfunction "CLK_IN_28") (pintype "input"))
    )
    (net (code "111") (name "unconnected-(U2-CLK_OUT-Pad1)") (class "Default")
      (node (ref "U2") (pin "1") (pinfunction "CLK_OUT_1") (pintype "output"))
    )
    (net (code "112") (name "unconnected-(U3-CLK_OUT-Pad1)") (class "Default")
      (node (ref "U3") (pin "1") (pinfunction "CLK_OUT_1") (pintype "output"))
    )
    (net (code "113") (name "unconnected-(U4-CLK_OUT-Pad1)") (class "Default")
      (node (ref "U4") (pin "1") (pinfunction "CLK_OUT_1") (pintype "output"))
    )
  )
)
